# motor_driver.net
KiCad netlist of a schematic drawn in EAGLE
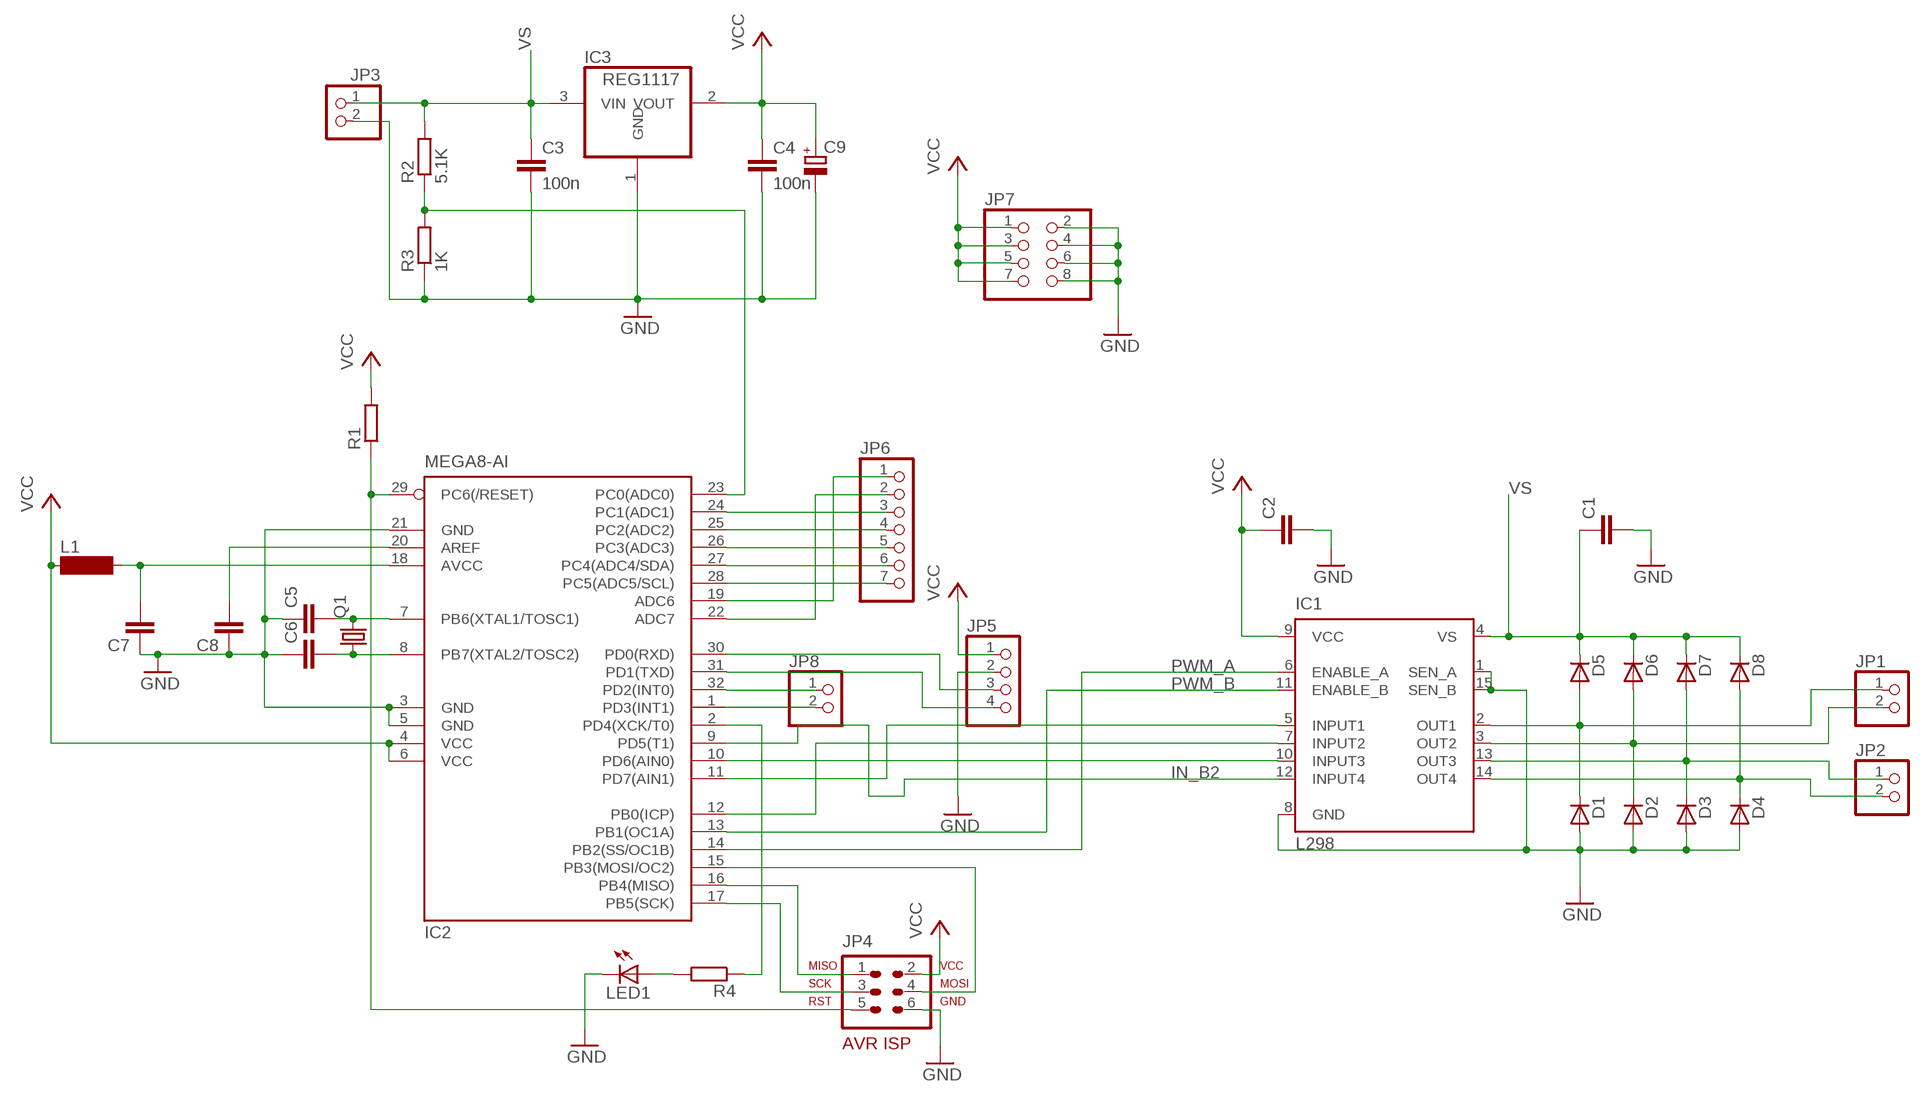
[diagram p0: schematic, sheet 1]

(export (version "E")
  (design (tool "Eeschema 10.0.6"))
  (components
    (comp (ref "C1")
      (value "C-EUC0805")
      (footprint "eagle-import:C0805")
      (libsource (lib "eagle-import") (part "C-EUC0805"))
    )
    (comp (ref "C2")
      (value "C-EUC0805")
      (footprint "eagle-import:C0805")
      (libsource (lib "eagle-import") (part "C-EUC0805"))
    )
    (comp (ref "C3")
      (value "100n")
      (footprint "eagle-import:C0805")
      (libsource (lib "eagle-import") (part "C-EUC0805"))
    )
    (comp (ref "C4")
      (value "100n")
      (footprint "eagle-import:C0805")
      (libsource (lib "eagle-import") (part "C-EUC0805"))
    )
    (comp (ref "C5")
      (value "C-EUC0805")
      (footprint "eagle-import:C0805")
      (libsource (lib "eagle-import") (part "C-EUC0805"))
    )
    (comp (ref "C6")
      (value "C-EUC0805")
      (footprint "eagle-import:C0805")
      (libsource (lib "eagle-import") (part "C-EUC0805"))
    )
    (comp (ref "C7")
      (value "C-EUC0805")
      (footprint "eagle-import:C0805")
      (libsource (lib "eagle-import") (part "C-EUC0805"))
    )
    (comp (ref "C8")
      (value "C-EUC0805")
      (footprint "eagle-import:C0805")
      (libsource (lib "eagle-import") (part "C-EUC0805"))
    )
    (comp (ref "C9")
      (value "CPOL-EUE2,5-6E")
      (footprint "eagle-import:E2,5-6E")
      (libsource (lib "eagle-import") (part "CPOL-EUE2,5-6E"))
    )
    (comp (ref "D1")
      (value "BYS10")
      (footprint "eagle-import:SOD106A")
      (fields (field (name "MPN") "BYS10/45"))
      (libsource (lib "eagle-import") (part "BYS10"))
    )
    (comp (ref "D2")
      (value "BYS10")
      (footprint "eagle-import:SOD106A")
      (fields (field (name "MPN") "BYS10/45"))
      (libsource (lib "eagle-import") (part "BYS10"))
    )
    (comp (ref "D3")
      (value "BYS10")
      (footprint "eagle-import:SOD106A")
      (fields (field (name "MPN") "BYS10/45"))
      (libsource (lib "eagle-import") (part "BYS10"))
    )
    (comp (ref "D4")
      (value "BYS10")
      (footprint "eagle-import:SOD106A")
      (fields (field (name "MPN") "BYS10/45"))
      (libsource (lib "eagle-import") (part "BYS10"))
    )
    (comp (ref "D5")
      (value "BYS10")
      (footprint "eagle-import:SOD106A")
      (fields (field (name "MPN") "BYS10/45"))
      (libsource (lib "eagle-import") (part "BYS10"))
    )
    (comp (ref "D6")
      (value "BYS10")
      (footprint "eagle-import:SOD106A")
      (fields (field (name "MPN") "BYS10/45"))
      (libsource (lib "eagle-import") (part "BYS10"))
    )
    (comp (ref "D7")
      (value "BYS10")
      (footprint "eagle-import:SOD106A")
      (fields (field (name "MPN") "BYS10/45"))
      (libsource (lib "eagle-import") (part "BYS10"))
    )
    (comp (ref "D8")
      (value "BYS10")
      (footprint "eagle-import:SOD106A")
      (fields (field (name "MPN") "BYS10/45"))
      (libsource (lib "eagle-import") (part "BYS10"))
    )
    (comp (ref "IC1")
      (value "L298")
      (footprint "eagle-import:MULTIWATT-15")
      (fields (field (name "MPN") "L298N"))
      (libsource (lib "eagle-import") (part "L298"))
    )
    (comp (ref "IC2")
      (value "MEGA8-AI")
      (footprint "eagle-import:TQFP32-08")
      (fields (field (name "MPN") "ATMEGA8-16AU"))
      (libsource (lib "eagle-import") (part "MEGA8-AI"))
    )
    (comp (ref "IC3")
      (value "REG1117")
      (footprint "eagle-import:SOT223")
      (libsource (lib "eagle-import") (part "REG1117"))
    )
    (comp (ref "JP1")
      (value "PINHD-1X2")
      (footprint "eagle-import:1X02")
      (libsource (lib "eagle-import") (part "PINHD-1X2"))
    )
    (comp (ref "JP2")
      (value "PINHD-1X2")
      (footprint "eagle-import:1X02")
      (libsource (lib "eagle-import") (part "PINHD-1X2"))
    )
    (comp (ref "JP3")
      (value "PINHD-1X2")
      (footprint "eagle-import:1X02")
      (libsource (lib "eagle-import") (part "PINHD-1X2"))
    )
    (comp (ref "JP4")
      (value "AVR-ISP-6VERT")
      (footprint "eagle-import:AVR-ISP-6")
      (libsource (lib "eagle-import") (part "AVR-ISP-6VERT"))
    )
    (comp (ref "JP5")
      (value "PINHD-1X4")
      (footprint "eagle-import:1X04")
      (libsource (lib "eagle-import") (part "PINHD-1X4"))
    )
    (comp (ref "JP6")
      (value "PINHD-1X7")
      (footprint "eagle-import:1X07")
      (libsource (lib "eagle-import") (part "PINHD-1X7"))
    )
    (comp (ref "JP7")
      (value "PINHD-2X4")
      (footprint "eagle-import:2X04")
      (libsource (lib "eagle-import") (part "PINHD-2X4"))
    )
    (comp (ref "JP8")
      (value "PINHD-1X2")
      (footprint "eagle-import:1X02")
      (libsource (lib "eagle-import") (part "PINHD-1X2"))
    )
    (comp (ref "L1")
      (value "SM-1206")
      (footprint "eagle-import:SM-1206")
      (libsource (lib "eagle-import") (part "SM-1206"))
    )
    (comp (ref "LED1")
      (value "LED3MM")
      (footprint "eagle-import:LED3MM")
      (libsource (lib "eagle-import") (part "LED3MM"))
    )
    (comp (ref "Q1")
      (value "CRYSTALHC49S")
      (footprint "eagle-import:HC49_S")
      (libsource (lib "eagle-import") (part "CRYSTALHC49S"))
    )
    (comp (ref "R1")
      (value "R-EU_M0805")
      (footprint "eagle-import:M0805")
      (libsource (lib "eagle-import") (part "R-EU_M0805"))
    )
    (comp (ref "R2")
      (value "5.1K")
      (footprint "eagle-import:M0805")
      (libsource (lib "eagle-import") (part "R-EU_M0805"))
    )
    (comp (ref "R3")
      (value "1K")
      (footprint "eagle-import:M0805")
      (libsource (lib "eagle-import") (part "R-EU_M0805"))
    )
    (comp (ref "R4")
      (value "R-EU_M0805")
      (footprint "eagle-import:M0805")
      (libsource (lib "eagle-import") (part "R-EU_M0805"))
    )
  )
  (nets
    (net (code "1") (name "/IN_B2") (class "Default")
      (node (ref "IC1") (pin "12") (pinfunction "INPUT4_12") (pintype "input"))
      (node (ref "IC2") (pin "9") (pinfunction "PD5(T1)_9") (pintype "bidirectional"))
    )
    (net (code "2") (name "/PWM_A") (class "Default")
      (node (ref "IC1") (pin "11") (pinfunction "ENABLE_B_11") (pintype "input"))
      (node (ref "IC2") (pin "13") (pinfunction "PB1(OC1A)_13") (pintype "bidirectional"))
    )
    (net (code "3") (name "/PWM_B") (class "Default")
      (node (ref "IC1") (pin "6") (pinfunction "ENABLE_A_6") (pintype "input"))
      (node (ref "IC2") (pin "14") (pinfunction "PB2(SS/OC1B)_14") (pintype "bidirectional"))
    )
    (net (code "4") (name "/VS") (class "Default")
      (node (ref "C1") (pin "1") (pinfunction "1_1") (pintype "passive"))
      (node (ref "C3") (pin "1") (pinfunction "1_1") (pintype "passive"))
      (node (ref "D5") (pin "K") (pinfunction "K_K") (pintype "passive"))
      (node (ref "D6") (pin "K") (pinfunction "K_K") (pintype "passive"))
      (node (ref "D7") (pin "K") (pinfunction "K_K") (pintype "passive"))
      (node (ref "D8") (pin "K") (pinfunction "K_K") (pintype "passive"))
      (node (ref "IC1") (pin "4") (pinfunction "VS_4") (pintype "power_in"))
      (node (ref "IC3") (pin "3") (pinfunction "VIN_3") (pintype "input"))
      (node (ref "JP3") (pin "1") (pinfunction "1_1") (pintype "passive"))
      (node (ref "R2") (pin "2") (pinfunction "2_2") (pintype "passive"))
    )
    (net (code "5") (name "GND") (class "Default")
      (node (ref "C1") (pin "2") (pinfunction "2_2") (pintype "passive"))
      (node (ref "C2") (pin "2") (pinfunction "2_2") (pintype "passive"))
      (node (ref "C3") (pin "2") (pinfunction "2_2") (pintype "passive"))
      (node (ref "C4") (pin "2") (pinfunction "2_2") (pintype "passive"))
      (node (ref "C5") (pin "1") (pinfunction "1_1") (pintype "passive"))
      (node (ref "C6") (pin "1") (pinfunction "1_1") (pintype "passive"))
      (node (ref "C7") (pin "1") (pinfunction "1_1") (pintype "passive"))
      (node (ref "C8") (pin "1") (pinfunction "1_1") (pintype "passive"))
      (node (ref "C9") (pin "-") (pinfunction "-_-") (pintype "passive"))
      (node (ref "D1") (pin "A") (pinfunction "A_A") (pintype "passive"))
      (node (ref "D2") (pin "A") (pinfunction "A_A") (pintype "passive"))
      (node (ref "D3") (pin "A") (pinfunction "A_A") (pintype "passive"))
      (node (ref "D4") (pin "A") (pinfunction "A_A") (pintype "passive"))
      (node (ref "IC1") (pin "1") (pinfunction "SEN_A_1") (pintype "input"))
      (node (ref "IC1") (pin "15") (pinfunction "SEN_B_15") (pintype "input"))
      (node (ref "IC1") (pin "8") (pinfunction "GND_8") (pintype "power_in"))
      (node (ref "IC2") (pin "21") (pinfunction "GND_21") (pintype "power_in"))
      (node (ref "IC2") (pin "3") (pinfunction "GND_3") (pintype "power_in"))
      (node (ref "IC2") (pin "5") (pinfunction "GND_5") (pintype "power_in"))
      (node (ref "IC3") (pin "1") (pinfunction "GND_1") (pintype "power_in"))
      (node (ref "JP3") (pin "2") (pinfunction "2_2") (pintype "passive"))
      (node (ref "JP4") (pin "6") (pinfunction "6_6") (pintype "passive"))
      (node (ref "JP5") (pin "2") (pinfunction "2_2") (pintype "passive"))
      (node (ref "JP7") (pin "2") (pinfunction "2_2") (pintype "passive"))
      (node (ref "JP7") (pin "4") (pinfunction "4_4") (pintype "passive"))
      (node (ref "JP7") (pin "6") (pinfunction "6_6") (pintype "passive"))
      (node (ref "JP7") (pin "8") (pinfunction "8_8") (pintype "passive"))
      (node (ref "LED1") (pin "K") (pinfunction "C_K") (pintype "passive"))
      (node (ref "R3") (pin "1") (pinfunction "1_1") (pintype "passive"))
    )
    (net (code "6") (name "Net-(IC1-INPUT1)") (class "Default")
      (node (ref "IC1") (pin "5") (pinfunction "INPUT1_5") (pintype "input"))
      (node (ref "IC2") (pin "11") (pinfunction "PD7(AIN1)_11") (pintype "bidirectional"))
    )
    (net (code "7") (name "Net-(IC1-INPUT2)") (class "Default")
      (node (ref "IC1") (pin "7") (pinfunction "INPUT2_7") (pintype "input"))
      (node (ref "IC2") (pin "12") (pinfunction "PB0(ICP)_12") (pintype "bidirectional"))
    )
    (net (code "8") (name "Net-(IC1-INPUT3)") (class "Default")
      (node (ref "IC1") (pin "10") (pinfunction "INPUT3_10") (pintype "input"))
      (node (ref "IC2") (pin "10") (pinfunction "PD6(AIN0)_10") (pintype "bidirectional"))
    )
    (net (code "9") (name "Net-(IC1-OUT1)") (class "Default")
      (node (ref "D1") (pin "K") (pinfunction "K_K") (pintype "passive"))
      (node (ref "D5") (pin "A") (pinfunction "A_A") (pintype "passive"))
      (node (ref "IC1") (pin "2") (pinfunction "OUT1_2") (pintype "output"))
      (node (ref "JP1") (pin "1") (pinfunction "1_1") (pintype "passive"))
    )
    (net (code "10") (name "Net-(IC1-OUT2)") (class "Default")
      (node (ref "D2") (pin "K") (pinfunction "K_K") (pintype "passive"))
      (node (ref "D6") (pin "A") (pinfunction "A_A") (pintype "passive"))
      (node (ref "IC1") (pin "3") (pinfunction "OUT2_3") (pintype "output"))
      (node (ref "JP1") (pin "2") (pinfunction "2_2") (pintype "passive"))
    )
    (net (code "11") (name "Net-(IC1-OUT3)") (class "Default")
      (node (ref "D3") (pin "K") (pinfunction "K_K") (pintype "passive"))
      (node (ref "D7") (pin "A") (pinfunction "A_A") (pintype "passive"))
      (node (ref "IC1") (pin "13") (pinfunction "OUT3_13") (pintype "output"))
      (node (ref "JP2") (pin "1") (pinfunction "1_1") (pintype "passive"))
    )
    (net (code "12") (name "Net-(IC1-OUT4)") (class "Default")
      (node (ref "D4") (pin "K") (pinfunction "K_K") (pintype "passive"))
      (node (ref "D8") (pin "A") (pinfunction "A_A") (pintype "passive"))
      (node (ref "IC1") (pin "14") (pinfunction "OUT4_14") (pintype "output"))
      (node (ref "JP2") (pin "2") (pinfunction "2_2") (pintype "passive"))
    )
    (net (code "13") (name "Net-(IC2-ADC6)") (class "Default")
      (node (ref "IC2") (pin "19") (pinfunction "ADC6_19") (pintype "bidirectional"))
      (node (ref "JP6") (pin "1") (pinfunction "1_1") (pintype "passive"))
    )
    (net (code "14") (name "Net-(IC2-ADC7)") (class "Default")
      (node (ref "IC2") (pin "22") (pinfunction "ADC7_22") (pintype "bidirectional"))
      (node (ref "JP6") (pin "2") (pinfunction "2_2") (pintype "passive"))
    )
    (net (code "15") (name "Net-(IC2-AREF)") (class "Default")
      (node (ref "C8") (pin "2") (pinfunction "2_2") (pintype "passive"))
      (node (ref "IC2") (pin "20") (pinfunction "AREF_20") (pintype "passive"))
    )
    (net (code "16") (name "Net-(IC2-AVCC)") (class "Default")
      (node (ref "C7") (pin "2") (pinfunction "2_2") (pintype "passive"))
      (node (ref "IC2") (pin "18") (pinfunction "AVCC_18") (pintype "power_in"))
      (node (ref "L1") (pin "2") (pinfunction "2_2") (pintype "passive"))
    )
    (net (code "17") (name "Net-(IC2-PB3(MOSI{slash}OC2))") (class "Default")
      (node (ref "IC2") (pin "15") (pinfunction "PB3(MOSI/OC2)_15") (pintype "bidirectional"))
      (node (ref "JP4") (pin "4") (pinfunction "4_4") (pintype "passive"))
    )
    (net (code "18") (name "Net-(IC2-PB4(MISO))") (class "Default")
      (node (ref "IC2") (pin "16") (pinfunction "PB4(MISO)_16") (pintype "bidirectional"))
      (node (ref "JP4") (pin "1") (pinfunction "1_1") (pintype "passive"))
    )
    (net (code "19") (name "Net-(IC2-PB5(SCK))") (class "Default")
      (node (ref "IC2") (pin "17") (pinfunction "PB5(SCK)_17") (pintype "bidirectional"))
      (node (ref "JP4") (pin "3") (pinfunction "3_3") (pintype "passive"))
    )
    (net (code "20") (name "Net-(IC2-PB6(XTAL1{slash}TOSC1))") (class "Default")
      (node (ref "C5") (pin "2") (pinfunction "2_2") (pintype "passive"))
      (node (ref "IC2") (pin "7") (pinfunction "PB6(XTAL1/TOSC1)_7") (pintype "bidirectional"))
      (node (ref "Q1") (pin "2") (pinfunction "2_2") (pintype "passive"))
    )
    (net (code "21") (name "Net-(IC2-PB7(XTAL2{slash}TOSC2))") (class "Default")
      (node (ref "C6") (pin "2") (pinfunction "2_2") (pintype "passive"))
      (node (ref "IC2") (pin "8") (pinfunction "PB7(XTAL2/TOSC2)_8") (pintype "bidirectional"))
      (node (ref "Q1") (pin "1") (pinfunction "1_1") (pintype "passive"))
    )
    (net (code "22") (name "Net-(IC2-PC0(ADC0))") (class "Default")
      (node (ref "IC2") (pin "23") (pinfunction "PC0(ADC0)_23") (pintype "bidirectional"))
      (node (ref "R2") (pin "1") (pinfunction "1_1") (pintype "passive"))
      (node (ref "R3") (pin "2") (pinfunction "2_2") (pintype "passive"))
    )
    (net (code "23") (name "Net-(IC2-PC1(ADC1))") (class "Default")
      (node (ref "IC2") (pin "24") (pinfunction "PC1(ADC1)_24") (pintype "bidirectional"))
      (node (ref "JP6") (pin "3") (pinfunction "3_3") (pintype "passive"))
    )
    (net (code "24") (name "Net-(IC2-PC2(ADC2))") (class "Default")
      (node (ref "IC2") (pin "25") (pinfunction "PC2(ADC2)_25") (pintype "bidirectional"))
      (node (ref "JP6") (pin "4") (pinfunction "4_4") (pintype "passive"))
    )
    (net (code "25") (name "Net-(IC2-PC3(ADC3))") (class "Default")
      (node (ref "IC2") (pin "26") (pinfunction "PC3(ADC3)_26") (pintype "bidirectional"))
      (node (ref "JP6") (pin "5") (pinfunction "5_5") (pintype "passive"))
    )
    (net (code "26") (name "Net-(IC2-PC4(ADC4{slash}SDA))") (class "Default")
      (node (ref "IC2") (pin "27") (pinfunction "PC4(ADC4/SDA)_27") (pintype "bidirectional"))
      (node (ref "JP6") (pin "6") (pinfunction "6_6") (pintype "passive"))
    )
    (net (code "27") (name "Net-(IC2-PC5(ADC5{slash}SCL))") (class "Default")
      (node (ref "IC2") (pin "28") (pinfunction "PC5(ADC5/SCL)_28") (pintype "bidirectional"))
      (node (ref "JP6") (pin "7") (pinfunction "7_7") (pintype "passive"))
    )
    (net (code "28") (name "Net-(IC2-PC6({slash}RESET))") (class "Default")
      (node (ref "IC2") (pin "29") (pinfunction "PC6(/RESET)_29") (pintype "bidirectional"))
      (node (ref "JP4") (pin "5") (pinfunction "5_5") (pintype "passive"))
      (node (ref "R1") (pin "1") (pinfunction "1_1") (pintype "passive"))
    )
    (net (code "29") (name "Net-(IC2-PD0(RXD))") (class "Default")
      (node (ref "IC2") (pin "30") (pinfunction "PD0(RXD)_30") (pintype "bidirectional"))
      (node (ref "JP5") (pin "3") (pinfunction "3_3") (pintype "passive"))
    )
    (net (code "30") (name "Net-(IC2-PD1(TXD))") (class "Default")
      (node (ref "IC2") (pin "31") (pinfunction "PD1(TXD)_31") (pintype "bidirectional"))
      (node (ref "JP5") (pin "4") (pinfunction "4_4") (pintype "passive"))
    )
    (net (code "31") (name "Net-(IC2-PD2(INT0))") (class "Default")
      (node (ref "IC2") (pin "32") (pinfunction "PD2(INT0)_32") (pintype "bidirectional"))
      (node (ref "JP8") (pin "1") (pinfunction "1_1") (pintype "passive"))
    )
    (net (code "32") (name "Net-(IC2-PD3(INT1))") (class "Default")
      (node (ref "IC2") (pin "1") (pinfunction "PD3(INT1)_1") (pintype "bidirectional"))
      (node (ref "JP8") (pin "2") (pinfunction "2_2") (pintype "passive"))
    )
    (net (code "33") (name "Net-(IC2-PD4(XCK{slash}T0))") (class "Default")
      (node (ref "IC2") (pin "2") (pinfunction "PD4(XCK/T0)_2") (pintype "bidirectional"))
      (node (ref "R4") (pin "1") (pinfunction "1_1") (pintype "passive"))
    )
    (net (code "34") (name "Net-(LED1-PadA)") (class "Default")
      (node (ref "LED1") (pin "A") (pinfunction "A_A") (pintype "passive"))
      (node (ref "R4") (pin "2") (pinfunction "2_2") (pintype "passive"))
    )
    (net (code "35") (name "VCC") (class "Default")
      (node (ref "C2") (pin "1") (pinfunction "1_1") (pintype "passive"))
      (node (ref "C4") (pin "1") (pinfunction "1_1") (pintype "passive"))
      (node (ref "C9") (pin "+") (pinfunction "+_+") (pintype "passive"))
      (node (ref "IC1") (pin "9") (pinfunction "VCC_9") (pintype "power_in"))
      (node (ref "IC2") (pin "4") (pinfunction "VCC_4") (pintype "power_in"))
      (node (ref "IC2") (pin "6") (pinfunction "VCC_6") (pintype "power_in"))
      (node (ref "IC3") (pin "2") (pinfunction "VOUT_2") (pintype "output"))
      (node (ref "JP4") (pin "2") (pinfunction "2_2") (pintype "passive"))
      (node (ref "JP5") (pin "1") (pinfunction "1_1") (pintype "passive"))
      (node (ref "JP7") (pin "1") (pinfunction "1_1") (pintype "passive"))
      (node (ref "JP7") (pin "3") (pinfunction "3_3") (pintype "passive"))
      (node (ref "JP7") (pin "5") (pinfunction "5_5") (pintype "passive"))
      (node (ref "JP7") (pin "7") (pinfunction "7_7") (pintype "passive"))
      (node (ref "L1") (pin "1") (pinfunction "1_1") (pintype "passive"))
      (node (ref "R1") (pin "2") (pinfunction "2_2") (pintype "passive"))
    )
  )
)
